# 3V3_buck.net
KiCad netlist of a schematic drawn in Altium Designer
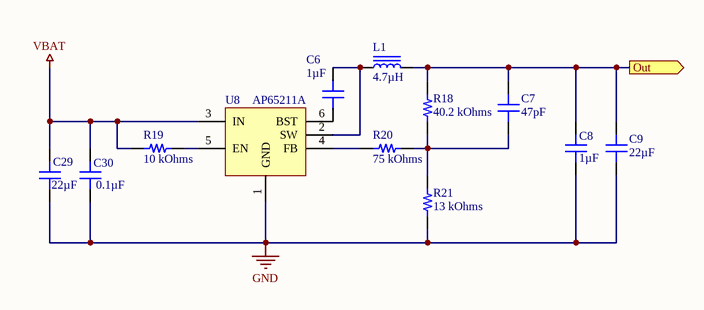
[diagram p0: 3V3_buck.SchDoc]

(export (version "E")
  (design (tool "Eeschema 10.0.6"))
  (components
    (comp (ref "C6")
      (value "1µF")
      (footprint "CAP 0603_1608")
      (description "CAP CER 1UF 25V X7R 0603")
      (fields
        (field (name "PART NUMBER") "GCJ188R71E105KA01D")
        (field (name "MANUFACTURER") "Murata Electronics")
      )
      (libsource (lib "Celestial Altium Library - altium_library") (part "Capacitor"))
    )
    (comp (ref "C7")
      (value "47pF")
      (footprint "CAP 0603_1608")
      (description "CAP CER 47PF 100V NP0 0603")
      (fields
        (field (name "PART NUMBER") "C1608NP02A470J080AA")
        (field (name "MANUFACTURER") "TDK Corporation")
      )
      (libsource (lib "Celestial Altium Library - altium_library") (part "Capacitor"))
    )
    (comp (ref "C8")
      (value "1µF")
      (footprint "CAP 0603_1608")
      (description "CAP CER 1UF 25V X7R 0603")
      (fields
        (field (name "PART NUMBER") "GCJ188R71E105KA01D")
        (field (name "MANUFACTURER") "Murata Electronics")
      )
      (libsource (lib "Celestial Altium Library - altium_library") (part "Capacitor"))
    )
    (comp (ref "C9")
      (value "22µF")
      (footprint "CAP 0805_2012")
      (description "CAP CER 22UF 16V X5R 0805")
      (fields
        (field (name "PART NUMBER") "CL21A226MOQNNNE")
        (field (name "MANUFACTURER") "Samsung Electro-Mechanics")
      )
      (libsource (lib "Celestial Altium Library - altium_library") (part "Capacitor"))
    )
    (comp (ref "C29")
      (value "22µF")
      (footprint "CAP 0805_2012")
      (description "CAP CER 10UF 25V X7S 0805")
      (fields
        (field (name "PART NUMBER") "C2012X7S1E106K125AC")
        (field (name "MANUFACTURER") "TDK Corporation")
      )
      (libsource (lib "Celestial Altium Library - altium_library") (part "Capacitor"))
    )
    (comp (ref "C30")
      (value "0.1µF")
      (footprint "CAP 0603_1608")
      (description "CAP CER 0.1UF 100V 0603 EPOXY")
      (fields
        (field (name "PART NUMBER") "GCG188R92A104KA03D")
        (field (name "MANUFACTURER") "Murata Electronics")
      )
      (libsource (lib "Celestial Altium Library - altium_library") (part "Capacitor"))
    )
    (comp (ref "L1")
      (value "4.7µH")
      (footprint "IND 1008_2520")
      (description "FIXED IND 4.7UH 1A 110 MOHM SMD")
      (fields (field (name "PART NUMBER") "MLP2520S4R7ST0S1") (field (name "MANUFACTURER") "TDK Corporation"))
      (libsource (lib "Celestial Altium Library - altium_library") (part "Inductor"))
    )
    (comp (ref "R18")
      (value "40.2 kOhms")
      (footprint "RES 0603_1608")
      (description "RES SMD 40.2KOHM 0.5% 1/10W 0603")
      (fields (field (name "PART NUMBER") "RT0603DRD0740K2L") (field (name "MANUFACTURER") "Yageo"))
      (libsource (lib "Celestial Altium Library - altium_library") (part "Resistor"))
    )
    (comp (ref "R19")
      (value "10 kOhms")
      (footprint "RES 0603_1608")
      (description "RES 10K OHM 0.1% 1/16W 0603")
      (fields
        (field (name "PART NUMBER") "RNCS0603BKE10K0")
        (field (name "MANUFACTURER") "Stackpole Electronics Inc")
      )
      (libsource (lib "Celestial Altium Library - altium_library") (part "Resistor"))
    )
    (comp (ref "R20")
      (value "75 kOhms")
      (footprint "RES 0603_1608")
      (description "RES SMD 75K OHM 5% 1/10W 0603")
      (fields (field (name "PART NUMBER") "CR0603-JW-753ELF") (field (name "MANUFACTURER") "Bourns Inc."))
      (libsource (lib "Celestial Altium Library - altium_library") (part "Resistor"))
    )
    (comp (ref "R21")
      (value "13 kOhms")
      (footprint "RES 0603_1608")
      (description "RES SMD 13K OHM 0.1% 1/10W 0603")
      (fields (field (name "PART NUMBER") "RG1608P-133-B-T5") (field (name "MANUFACTURER") "Susumu"))
      (libsource (lib "Celestial Altium Library - altium_library") (part "Resistor"))
    )
    (comp (ref "U8")
      (value "AP65211A")
      (footprint "TSOT-26-6")
      (description "ADJ step down Buck")
      (libsource (lib "IC") (part "AP65211A"))
    )
  )
  (nets
    (net (code "1") (name "/Out") (class "Default")
      (node (ref "C7") (pin "2") (pinfunction "2_2") (pintype "passive"))
      (node (ref "C8") (pin "2") (pinfunction "2_2") (pintype "passive"))
      (node (ref "C9") (pin "2") (pinfunction "2_2") (pintype "passive"))
      (node (ref "L1") (pin "2") (pinfunction "2_2") (pintype "passive"))
      (node (ref "R18") (pin "2") (pinfunction "2_2") (pintype "passive"))
    )
    (net (code "2") (name "GND") (class "Default")
      (node (ref "C29") (pin "1") (pinfunction "1_1") (pintype "passive"))
      (node (ref "C30") (pin "2") (pinfunction "2_2") (pintype "passive"))
      (node (ref "C8") (pin "1") (pinfunction "1_1") (pintype "passive"))
      (node (ref "C9") (pin "1") (pinfunction "1_1") (pintype "passive"))
      (node (ref "R21") (pin "1") (pinfunction "1_1") (pintype "passive"))
      (node (ref "U8") (pin "1") (pinfunction "GND_1") (pintype "passive"))
    )
    (net (code "3") (name "Net-(C7-Pad1)") (class "Default")
      (node (ref "C7") (pin "1") (pinfunction "1_1") (pintype "passive"))
      (node (ref "R18") (pin "1") (pinfunction "1_1") (pintype "passive"))
      (node (ref "R20") (pin "2") (pinfunction "2_2") (pintype "passive"))
      (node (ref "R21") (pin "2") (pinfunction "2_2") (pintype "passive"))
    )
    (net (code "4") (name "Net-(U8-BST)") (class "Default")
      (node (ref "C6") (pin "2") (pinfunction "2_2") (pintype "passive"))
      (node (ref "U8") (pin "6") (pinfunction "BST_6") (pintype "passive"))
    )
    (net (code "5") (name "Net-(U8-EN)") (class "Default")
      (node (ref "R19") (pin "1") (pinfunction "1_1") (pintype "passive"))
      (node (ref "U8") (pin "5") (pinfunction "EN_5") (pintype "passive"))
    )
    (net (code "6") (name "Net-(U8-FB)") (class "Default")
      (node (ref "R20") (pin "1") (pinfunction "1_1") (pintype "passive"))
      (node (ref "U8") (pin "4") (pinfunction "FB_4") (pintype "passive"))
    )
    (net (code "7") (name "Net-(U8-SW)") (class "Default")
      (node (ref "C6") (pin "1") (pinfunction "1_1") (pintype "passive"))
      (node (ref "L1") (pin "1") (pinfunction "1_1") (pintype "passive"))
      (node (ref "U8") (pin "2") (pinfunction "SW_2") (pintype "passive"))
    )
    (net (code "8") (name "VBAT") (class "Default")
      (node (ref "C29") (pin "2") (pinfunction "2_2") (pintype "passive"))
      (node (ref "C30") (pin "1") (pinfunction "1_1") (pintype "passive"))
      (node (ref "R19") (pin "2") (pinfunction "2_2") (pintype "passive"))
      (node (ref "U8") (pin "3") (pinfunction "IN_3") (pintype "passive"))
    )
  )
)
